# 11_-_COMMUNICATION.net
KiCad netlist of a schematic drawn in Altium Designer
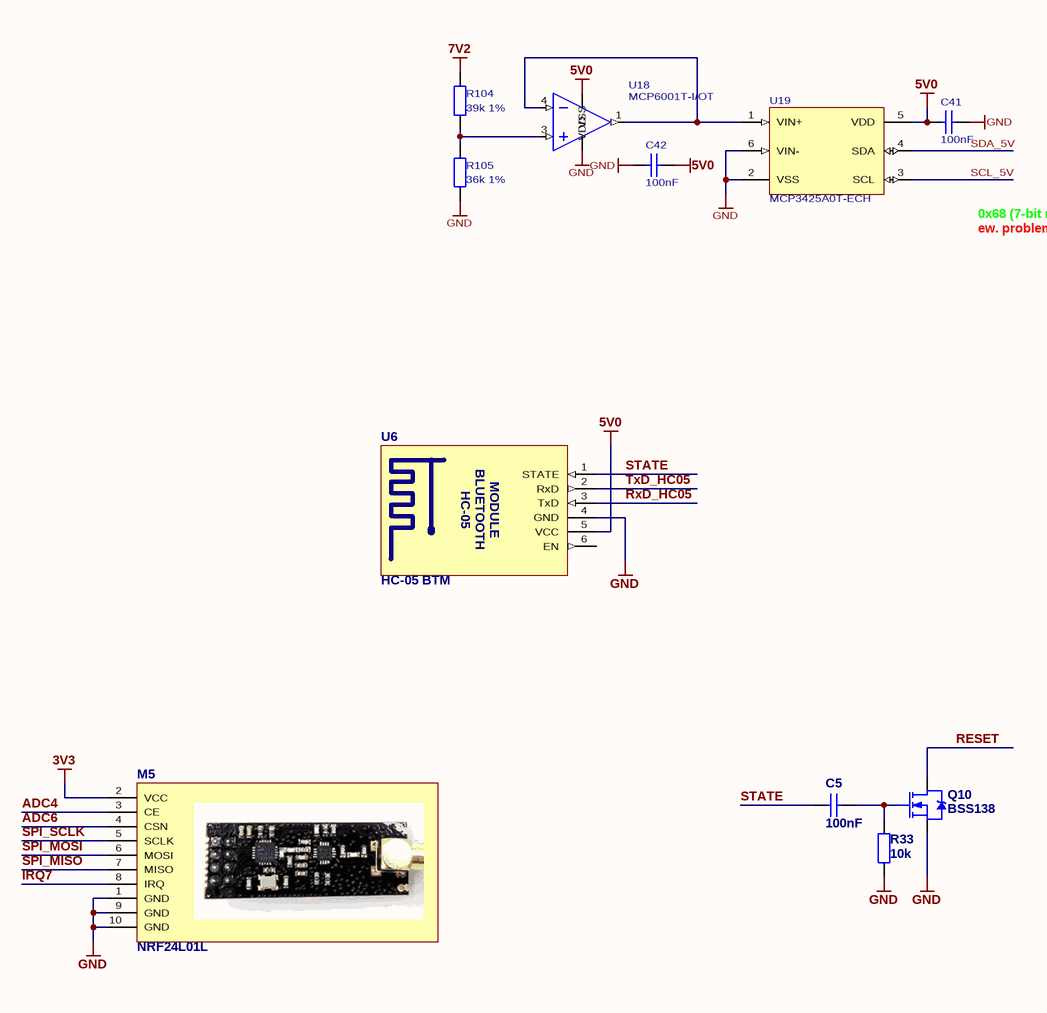
[diagram p0: [11] - COMMUNICATION.SchDoc]

(export (version "E")
  (design (tool "Eeschema 10.0.6"))
  (components
    (comp (ref "C5")
      (value "100nF")
      (footprint "C0805")
      (description "Capacitor")
      (libsource (lib "capacitors") (part "Cap"))
    )
    (comp (ref "C41")
      (value "100nF")
      (footprint "C0805")
      (description "Capacitor")
      (libsource (lib "capacitors") (part "Cap"))
    )
    (comp (ref "C42")
      (value "100nF")
      (footprint "C0805")
      (description "Capacitor")
      (libsource (lib "capacitors") (part "Cap"))
    )
    (comp (ref "M5")
      (value "NRF24L01L")
      (footprint "NRF24L01L")
      (description "Long Range Wireless Module R2 (1.1KM, PA+SMA)")
      (libsource (lib "wireless_modules") (part "NRF24L01L"))
    )
    (comp (ref "Q10")
      (value "BSS138")
      (footprint "SOT-23")
      (description "N-Channel Enhancement Mode Vertical DMOS FET")
      (fields (field (name "PUBLISHER") "Altium Limited"))
      (libsource (lib "transistors_mos") (part "BSS138"))
    )
    (comp (ref "R33")
      (value "10k")
      (footprint "R0805")
      (description "Resistor")
      (libsource (lib "") (part "Res_1"))
    )
    (comp (ref "R104")
      (value "39k 1%")
      (footprint "R0805")
      (description "Resistor")
      (libsource (lib "resistors") (part "Res"))
    )
    (comp (ref "R105")
      (value "36k 1%")
      (footprint "R0805")
      (description "Resistor")
      (libsource (lib "resistors") (part "Res"))
    )
    (comp (ref "U6")
      (value "HC-05 BTM")
      (footprint "HC-05_H_2")
      (description "HC-05 Bluetooth Module")
      (libsource (lib "wireless_modules") (part "HC-05_BTM"))
    )
    (comp (ref "U18")
      (value "MCP6001T-I/OT")
      (footprint "SOT-23-5")
      (description "Rail-to-rail, 1MHz, 100uA Op Amp")
      (libsource (lib "opamps") (part "MCP6001T-I/OT"))
    )
    (comp (ref "U19")
      (value "MCP3425A0T-ECH")
      (footprint "SOT-23-6")
      (description "16-Bit Analog-to-Digital Converter with I2C Interface and On-Board Reference")
      (libsource (lib "ad_converters") (part "MCP3425A0T-ECH"))
    )
  )
  (nets
    (net (code "1") (name "/ADC4") (class "Default")
      (node (ref "M5") (pin "3") (pinfunction "CE_3") (pintype "passive"))
    )
    (net (code "2") (name "/ADC6") (class "Default")
      (node (ref "M5") (pin "4") (pinfunction "CSN_4") (pintype "passive"))
    )
    (net (code "3") (name "/IRQ7") (class "Default")
      (node (ref "M5") (pin "8") (pinfunction "IRQ_8") (pintype "passive"))
    )
    (net (code "4") (name "/RESET") (class "Default")
      (node (ref "Q10") (pin "3") (pinfunction "D_3") (pintype "passive"))
    )
    (net (code "5") (name "/RxD_HC05") (class "Default")
      (node (ref "U6") (pin "3") (pinfunction "TxD_3") (pintype "input"))
    )
    (net (code "6") (name "/SCL_5V") (class "Default")
      (node (ref "U19") (pin "3") (pinfunction "SCL_3") (pintype "bidirectional"))
    )
    (net (code "7") (name "/SDA_5V") (class "Default")
      (node (ref "U19") (pin "4") (pinfunction "SDA_4") (pintype "bidirectional"))
    )
    (net (code "8") (name "/SPI_MISO") (class "Default")
      (node (ref "M5") (pin "7") (pinfunction "MISO_7") (pintype "passive"))
    )
    (net (code "9") (name "/SPI_MOSI") (class "Default")
      (node (ref "M5") (pin "6") (pinfunction "MOSI_6") (pintype "passive"))
    )
    (net (code "10") (name "/SPI_SCLK") (class "Default")
      (node (ref "M5") (pin "5") (pinfunction "SCLK_5") (pintype "passive"))
    )
    (net (code "11") (name "/STATE") (class "Default")
      (node (ref "C5") (pin "1") (pinfunction "1_1") (pintype "passive"))
      (node (ref "U6") (pin "1") (pinfunction "STATE_1") (pintype "input"))
    )
    (net (code "12") (name "/TxD_HC05") (class "Default")
      (node (ref "U6") (pin "2") (pinfunction "RxD_2") (pintype "output"))
    )
    (net (code "13") (name "3V3") (class "Default")
      (node (ref "M5") (pin "2") (pinfunction "VCC_2") (pintype "passive"))
    )
    (net (code "14") (name "5V0") (class "Default")
      (node (ref "C41") (pin "1") (pinfunction "1_1") (pintype "passive"))
      (node (ref "C42") (pin "1") (pinfunction "1_1") (pintype "passive"))
      (node (ref "U18") (pin "5") (pinfunction "VDD_5") (pintype "power_in"))
      (node (ref "U19") (pin "5") (pinfunction "VDD_5") (pintype "power_in"))
      (node (ref "U6") (pin "5") (pinfunction "VCC_5") (pintype "power_in"))
    )
    (net (code "15") (name "7V2") (class "Default")
      (node (ref "R104") (pin "1") (pinfunction "1_1") (pintype "passive"))
    )
    (net (code "16") (name "GND") (class "Default")
      (node (ref "C41") (pin "2") (pinfunction "2_2") (pintype "passive"))
      (node (ref "C42") (pin "2") (pinfunction "2_2") (pintype "passive"))
      (node (ref "M5") (pin "1") (pinfunction "GND_1") (pintype "passive"))
      (node (ref "M5") (pin "10") (pinfunction "GND_10") (pintype "passive"))
      (node (ref "M5") (pin "9") (pinfunction "GND_9") (pintype "passive"))
      (node (ref "Q10") (pin "2") (pinfunction "S_2") (pintype "passive"))
      (node (ref "R105") (pin "2") (pinfunction "2_2") (pintype "passive"))
      (node (ref "R33") (pin "2") (pinfunction "2_2") (pintype "passive"))
      (node (ref "U18") (pin "2") (pinfunction "VSS_2") (pintype "power_in"))
      (node (ref "U19") (pin "2") (pinfunction "VSS_2") (pintype "power_in"))
      (node (ref "U19") (pin "6") (pinfunction "VIN-_6") (pintype "input"))
      (node (ref "U6") (pin "4") (pinfunction "GND_4") (pintype "power_in"))
    )
    (net (code "17") (name "Net-(Q10-G)") (class "Default")
      (node (ref "C5") (pin "2") (pinfunction "2_2") (pintype "passive"))
      (node (ref "Q10") (pin "1") (pinfunction "G_1") (pintype "passive"))
      (node (ref "R33") (pin "1") (pinfunction "1_1") (pintype "passive"))
    )
    (net (code "18") (name "Net-(U18-IN+)") (class "Default")
      (node (ref "R104") (pin "2") (pinfunction "2_2") (pintype "passive"))
      (node (ref "R105") (pin "1") (pinfunction "1_1") (pintype "passive"))
      (node (ref "U18") (pin "3") (pinfunction "IN+_3") (pintype "input"))
    )
    (net (code "19") (name "Net-(U18-IN-)") (class "Default")
      (node (ref "U18") (pin "1") (pinfunction "OUT_1") (pintype "output"))
      (node (ref "U18") (pin "4") (pinfunction "IN-_4") (pintype "input"))
      (node (ref "U19") (pin "1") (pinfunction "VIN+_1") (pintype "input"))
    )
    (net (code "20") (name "unconnected-(U6-EN-Pad6)") (class "Default")
      (node (ref "U6") (pin "6") (pinfunction "EN_6") (pintype "output"))
    )
  )
)
